# ADG719-Breakout.net
KiCad netlist of a schematic drawn in EAGLE
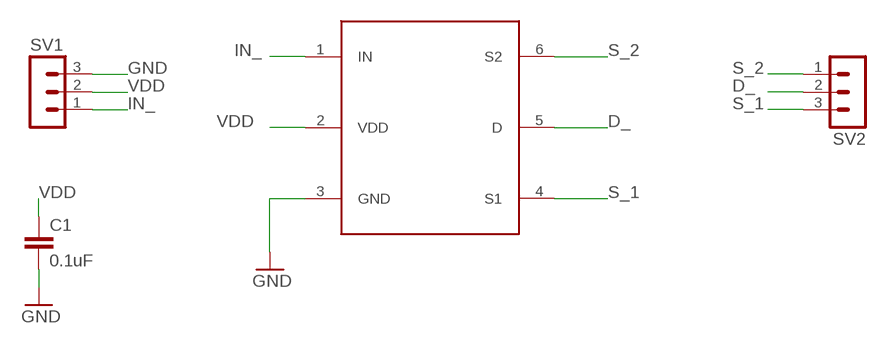
[diagram p0: schematic, sheet 1]

(export (version "E")
  (design (tool "Eeschema 10.0.6"))
  (components
    (comp (ref "C1")
      (value "0.1uF")
      (footprint "eagle-import:C0805")
      (libsource (lib "eagle-import") (part "C-EUC0805"))
    )
    (comp (ref "SV1")
      (value "MA03-1")
      (footprint "eagle-import:MA03-1")
      (libsource (lib "eagle-import") (part "MA03-1"))
    )
    (comp (ref "SV2")
      (value "MA03-1")
      (footprint "eagle-import:MA03-1")
      (libsource (lib "eagle-import") (part "MA03-1"))
    )
    (comp (ref "U$1")
      (value "ADG719")
      (footprint "eagle-import:ADG719")
      (libsource (lib "eagle-import") (part "ADG719"))
    )
  )
  (nets
    (net (code "1") (name "/D_") (class "Default")
      (node (ref "SV2") (pin "2") (pinfunction "2_2") (pintype "passive"))
      (node (ref "U$1") (pin "5") (pinfunction "D_5") (pintype "bidirectional"))
    )
    (net (code "2") (name "/IN_") (class "Default")
      (node (ref "SV1") (pin "1") (pinfunction "1_1") (pintype "passive"))
      (node (ref "U$1") (pin "1") (pinfunction "IN_1") (pintype "bidirectional"))
    )
    (net (code "3") (name "/S_1") (class "Default")
      (node (ref "SV2") (pin "3") (pinfunction "3_3") (pintype "passive"))
      (node (ref "U$1") (pin "4") (pinfunction "S1_4") (pintype "bidirectional"))
    )
    (net (code "4") (name "/S_2") (class "Default")
      (node (ref "SV2") (pin "1") (pinfunction "1_1") (pintype "passive"))
      (node (ref "U$1") (pin "6") (pinfunction "S2_6") (pintype "bidirectional"))
    )
    (net (code "5") (name "/VDD") (class "Default")
      (node (ref "C1") (pin "1") (pinfunction "1_1") (pintype "passive"))
      (node (ref "SV1") (pin "2") (pinfunction "2_2") (pintype "passive"))
      (node (ref "U$1") (pin "2") (pinfunction "VDD_2") (pintype "bidirectional"))
    )
    (net (code "6") (name "GND") (class "Default")
      (node (ref "C1") (pin "2") (pinfunction "2_2") (pintype "passive"))
      (node (ref "SV1") (pin "3") (pinfunction "3_3") (pintype "passive"))
      (node (ref "U$1") (pin "3") (pinfunction "GND_3") (pintype "bidirectional"))
    )
  )
)
